# Sheet1.net
KiCad netlist of a schematic drawn in Altium Designer
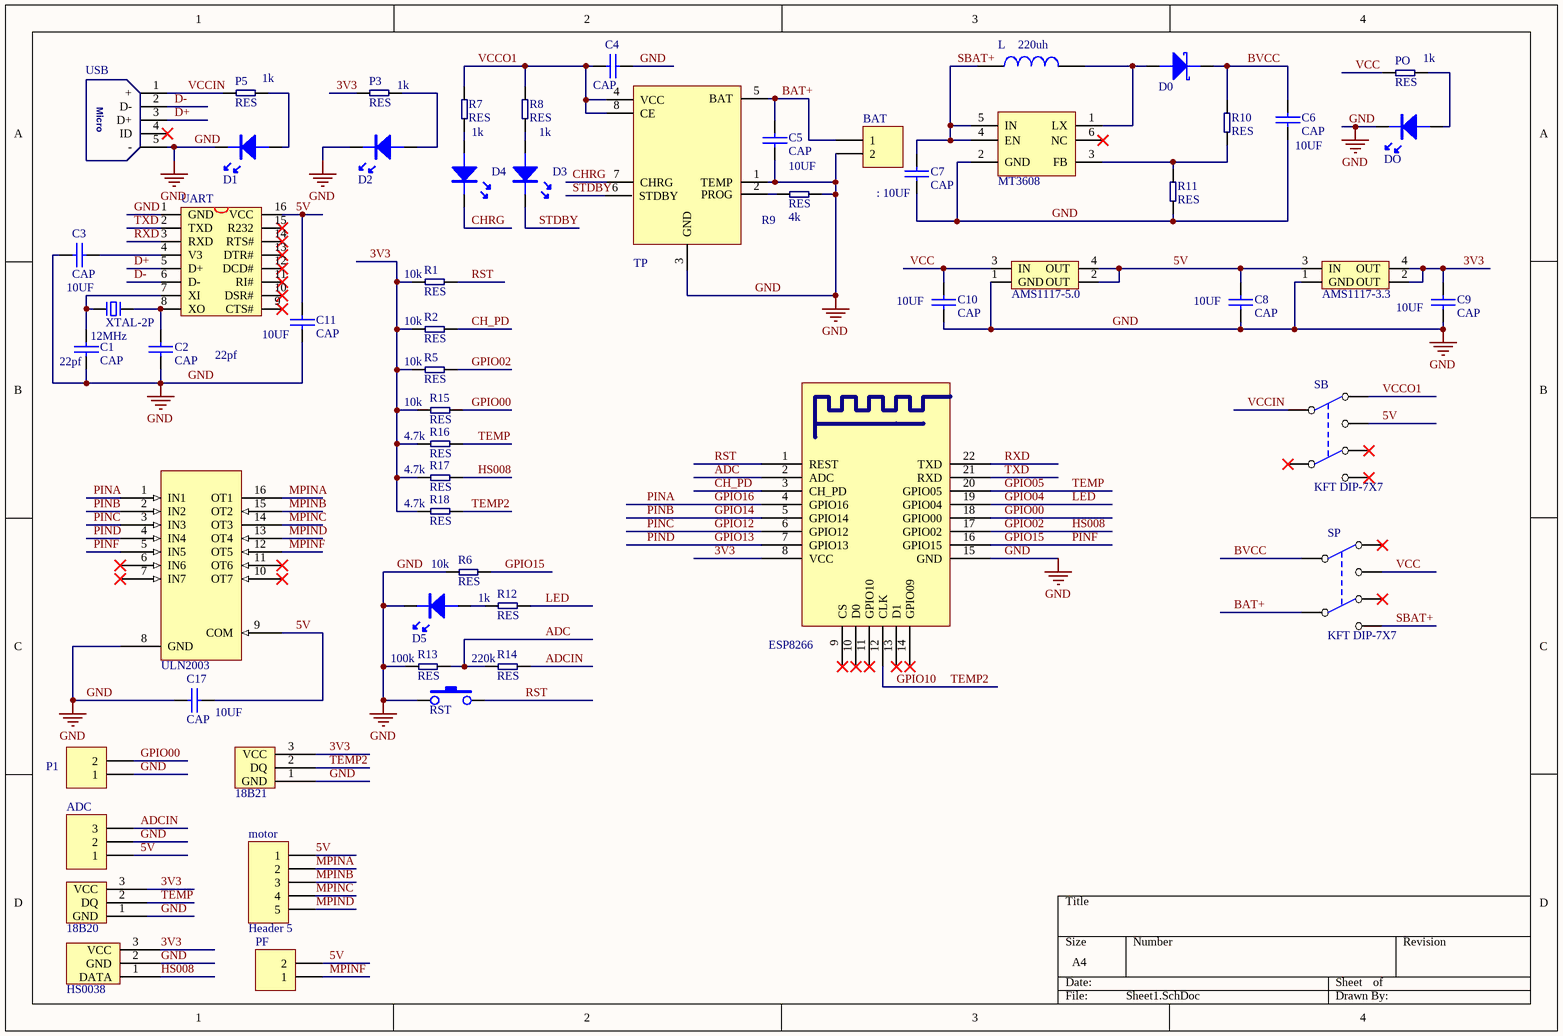
[diagram p0: Sheet1.SchDoc]

(export (version "E")
  (design (tool "Eeschema 10.0.6"))
  (components
    (comp (ref "18B20")
      (value "DS18B20")
      (footprint "DS18B20")
      (libsource (lib "MiniSTM32 V3.0封装库") (part "DS18B20"))
    )
    (comp (ref "18B21")
      (value "DS18B20")
      (footprint "DS18B20")
      (libsource (lib "MiniSTM32 V3.0封装库") (part "DS18B20"))
    )
    (comp (ref "ADC")
      (value "Header 3")
      (footprint "HDR1X3")
      (description "Header, 3-Pin")
      (fields (field (name "PUBLISHER") "Altium Limited"))
      (libsource (lib "Miscellaneous Connectors") (part "Header 3"))
    )
    (comp (ref "AMS117")
      (value "AMS1117-3.3")
      (footprint "AMS1117")
      (libsource (lib "MiniSTM32 V3.0封装库") (part "AMS1117"))
    )
    (comp (ref "AMS117-1")
      (value "AMS1117-5.0")
      (footprint "AMS1117")
      (libsource (lib "MiniSTM32 V3.0封装库") (part "AMS1117"))
    )
    (comp (ref "BAT")
      (value "Header 2")
      (footprint "HDR1X2")
      (description "Header, 2-Pin")
      (fields (field (name "PUBLISHER") "Altium Limited"))
      (libsource (lib "Miscellaneous Connectors") (part "Header 2"))
    )
    (comp (ref "C1")
      (value "CAP")
      (footprint "0805C")
      (description "无极性电容")
      (fields (field (name "ALTIUM_UNNAMED_1") "22pf"))
      (libsource (lib "电容") (part "CAP"))
    )
    (comp (ref "C2")
      (value "CAP")
      (footprint "0805C")
      (description "无极性电容")
      (fields (field (name "ALTIUM_UNNAMED_1") "22pf"))
      (libsource (lib "电容") (part "CAP"))
    )
    (comp (ref "C3")
      (value "CAP")
      (footprint "0805C")
      (description "无极性电容")
      (fields (field (name "ALTIUM_UNNAMED_1") "10UF"))
      (libsource (lib "电容") (part "CAP"))
    )
    (comp (ref "C4")
      (value "CAP")
      (footprint "0805C")
      (description "无极性电容")
      (libsource (lib "电容") (part "CAP"))
    )
    (comp (ref "C5")
      (value "CAP")
      (footprint "0805C")
      (description "无极性电容")
      (fields (field (name "ALTIUM_UNNAMED_1") "10UF"))
      (libsource (lib "电容") (part "CAP"))
    )
    (comp (ref "C6")
      (value "CAP")
      (footprint "0805C")
      (description "无极性电容")
      (fields (field (name "ALTIUM_UNNAMED_1") "10UF"))
      (libsource (lib "电容") (part "CAP"))
    )
    (comp (ref "C7")
      (value "CAP")
      (footprint "0805C")
      (description "无极性电容")
      (fields (field (name "ALTIUM_UNNAMED_1") "10UF"))
      (libsource (lib "电容") (part "CAP"))
    )
    (comp (ref "C8")
      (value "CAP")
      (footprint "0805C")
      (description "无极性电容")
      (fields (field (name "ALTIUM_UNNAMED_1") "10UF"))
      (libsource (lib "电容") (part "CAP"))
    )
    (comp (ref "C9")
      (value "CAP")
      (footprint "0805C")
      (description "无极性电容")
      (fields (field (name "ALTIUM_UNNAMED_1") "10UF"))
      (libsource (lib "电容") (part "CAP"))
    )
    (comp (ref "C10")
      (value "CAP")
      (footprint "0805C")
      (description "无极性电容")
      (fields (field (name "ALTIUM_UNNAMED_1") "10UF"))
      (libsource (lib "电容") (part "CAP"))
    )
    (comp (ref "C11")
      (value "CAP")
      (footprint "0805C")
      (description "无极性电容")
      (fields (field (name "ALTIUM_UNNAMED_1") "10UF"))
      (libsource (lib "电容") (part "CAP"))
    )
    (comp (ref "C17")
      (value "CAP")
      (footprint "0805C")
      (description "无极性电容")
      (fields (field (name "ALTIUM_UNNAMED_1") "10UF"))
      (libsource (lib "电容") (part "CAP"))
    )
    (comp (ref "D0")
      (value "DIODE SCHOTTKY")
      (footprint "SMA/DO-214AC")
      (description "肖特基二极管")
      (libsource (lib "二极管") (part "DIODE SCHOTTKY"))
    )
    (comp (ref "D1") (value "LED") (footprint "LED-0805R") (libsource (lib "LED") (part "LED")))
    (comp (ref "D2") (value "LED") (footprint "LED-0805R") (libsource (lib "LED") (part "LED")))
    (comp (ref "D3") (value "LED") (footprint "LED-0805R") (libsource (lib "LED") (part "LED")))
    (comp (ref "D4") (value "LED") (footprint "LED-0805R") (libsource (lib "LED") (part "LED")))
    (comp (ref "D5") (value "LED") (footprint "LED-0805R") (libsource (lib "LED") (part "LED")))
    (comp (ref "DO") (value "LED") (footprint "LED-0805R") (libsource (lib "LED") (part "LED")))
    (comp (ref "ESP8266") (value "ESP8266") (footprint "ESP_12") (libsource (lib "传感器") (part "ESP8266")))
    (comp (ref "HS0038")
      (value "HS0038")
      (footprint "HS0038")
      (libsource (lib "MiniSTM32 V3.0封装库") (part "HS0038"))
    )
    (comp (ref "L")
      (value "INDUCTOR")
      (footprint "CD54")
      (fields (field (name "ALTIUM_UNNAMED_1") "220uh"))
      (libsource (lib "电感") (part "INDUCTOR"))
    )
    (comp (ref "motor")
      (value "Header 5")
      (footprint "HDR1X5")
      (description "Header, 5-Pin")
      (fields (field (name "PUBLISHER") "Altium Limited"))
      (libsource (lib "Miscellaneous Connectors") (part "Header 5"))
    )
    (comp (ref "MT") (value "MT3608") (footprint "SOT23-6") (libsource (lib "Schlib1") (part "MT3608")))
    (comp (ref "P1")
      (value "Header 2")
      (footprint "HDR1X2")
      (description "Header, 2-Pin")
      (fields (field (name "PUBLISHER") "Altium Limited"))
      (libsource (lib "") (part "Header 2_1"))
    )
    (comp (ref "P3")
      (value "RES")
      (footprint "0805R")
      (fields (field (name "ALTIUM_UNNAMED_1") "1k"))
      (libsource (lib "Schlib1") (part "RES"))
    )
    (comp (ref "P5")
      (value "RES")
      (footprint "0805R")
      (fields (field (name "ALTIUM_UNNAMED_1") "1k"))
      (libsource (lib "Schlib1") (part "RES"))
    )
    (comp (ref "PF")
      (value "Header 2")
      (footprint "HDR1X2")
      (description "Header, 2-Pin")
      (fields (field (name "PUBLISHER") "Altium Limited"))
      (libsource (lib "") (part "Header 2_1"))
    )
    (comp (ref "PO")
      (value "RES")
      (footprint "0805R")
      (fields (field (name "ALTIUM_UNNAMED_1") "1k"))
      (libsource (lib "Schlib1") (part "RES"))
    )
    (comp (ref "R1")
      (value "RES")
      (footprint "0805R")
      (fields (field (name "ALTIUM_UNNAMED_1") "10k"))
      (libsource (lib "Schlib1") (part "RES"))
    )
    (comp (ref "R2")
      (value "RES")
      (footprint "0805R")
      (fields (field (name "ALTIUM_UNNAMED_1") "10k"))
      (libsource (lib "Schlib1") (part "RES"))
    )
    (comp (ref "R5")
      (value "RES")
      (footprint "0805R")
      (fields (field (name "ALTIUM_UNNAMED_1") "10k"))
      (libsource (lib "Schlib1") (part "RES"))
    )
    (comp (ref "R6")
      (value "RES")
      (footprint "0805R")
      (fields (field (name "ALTIUM_UNNAMED_1") "10k"))
      (libsource (lib "Schlib1") (part "RES"))
    )
    (comp (ref "R7")
      (value "RES")
      (footprint "0805R")
      (fields (field (name "ALTIUM_UNNAMED_1") "1k"))
      (libsource (lib "Schlib1") (part "RES"))
    )
    (comp (ref "R8")
      (value "RES")
      (footprint "0805R")
      (fields (field (name "ALTIUM_UNNAMED_1") "1k"))
      (libsource (lib "Schlib1") (part "RES"))
    )
    (comp (ref "R9")
      (value "RES")
      (footprint "0805R")
      (fields (field (name "ALTIUM_UNNAMED_1") "4k"))
      (libsource (lib "Schlib1") (part "RES"))
    )
    (comp (ref "R10") (value "RES") (footprint "0805R") (libsource (lib "Schlib1") (part "RES")))
    (comp (ref "R11") (value "RES") (footprint "0805R") (libsource (lib "Schlib1") (part "RES")))
    (comp (ref "R12")
      (value "RES")
      (footprint "0805R")
      (fields (field (name "ALTIUM_UNNAMED_1") "1k"))
      (libsource (lib "Schlib1") (part "RES"))
    )
    (comp (ref "R13")
      (value "RES")
      (footprint "0805R")
      (fields (field (name "ALTIUM_UNNAMED_1") "100k"))
      (libsource (lib "Schlib1") (part "RES"))
    )
    (comp (ref "R14")
      (value "RES")
      (footprint "0805R")
      (fields (field (name "ALTIUM_UNNAMED_1") "220k"))
      (libsource (lib "Schlib1") (part "RES"))
    )
    (comp (ref "R15")
      (value "RES")
      (footprint "0805R")
      (fields (field (name "ALTIUM_UNNAMED_1") "10k"))
      (libsource (lib "Schlib1") (part "RES"))
    )
    (comp (ref "R16")
      (value "RES")
      (footprint "0805R")
      (fields (field (name "ALTIUM_UNNAMED_1") "4.7k"))
      (libsource (lib "Schlib1") (part "RES"))
    )
    (comp (ref "R17")
      (value "RES")
      (footprint "0805R")
      (fields (field (name "ALTIUM_UNNAMED_1") "4.7k"))
      (libsource (lib "Schlib1") (part "RES"))
    )
    (comp (ref "R18")
      (value "RES")
      (footprint "0805R")
      (fields (field (name "ALTIUM_UNNAMED_1") "4.7k"))
      (libsource (lib "Schlib1") (part "RES"))
    )
    (comp (ref "RST") (value "KEY") (footprint "DIP-3X6X4.3") (libsource (lib "轻触开关") (part "KEY")))
    (comp (ref "SB")
      (value "KFT DIP-7X7")
      (footprint "KFT DIP-7X7")
      (libsource (lib "电源开关") (part "KFT DIP-7X7"))
    )
    (comp (ref "SP")
      (value "KFT DIP-7X7")
      (footprint "KFT DIP-7X7")
      (libsource (lib "电源开关") (part "KFT DIP-7X7"))
    )
    (comp (ref "TP") (value "TP4056") (footprint "SOP-8") (libsource (lib "Schlib1") (part "TP4056")))
    (comp (ref "UART")
      (value "CH340G")
      (footprint "SOP16M")
      (description "USB2UART")
      (libsource (lib "MiniSTM32 V3.0封装库") (part "CH340G"))
    )
    (comp (ref "ULN2003") (value "ULN2003") (footprint "SOP16") (libsource (lib "未分类IC") (part "ULN2003")))
    (comp (ref "USB")
      (value "Micro-USB")
      (footprint "USB-MICRO_A")
      (libsource (lib "USB") (part "Micro-USB"))
    )
    (comp (ref "X")
      (value "XTAL-2P")
      (footprint "OSC HC-49S")
      (description "2脚无源脚晶振")
      (fields (field (name "ALTIUM_UNNAMED_1") "12MHz"))
      (libsource (lib "晶振") (part "XTAL-2P"))
    )
  )
  (nets
    (net (code "1") (name "/3V3") (class "Default")
      (node (ref "18B20") (pin "3") (pinfunction "VCC_3") (pintype "passive"))
      (node (ref "18B21") (pin "3") (pinfunction "VCC_3") (pintype "passive"))
      (node (ref "AMS117") (pin "2") (pinfunction "OUT_2") (pintype "passive"))
      (node (ref "AMS117") (pin "4") (pinfunction "OUT_4") (pintype "passive"))
      (node (ref "C9") (pin "2") (pinfunction "2_2") (pintype "passive"))
      (node (ref "ESP8266") (pin "8") (pinfunction "VCC_8") (pintype "passive"))
      (node (ref "HS0038") (pin "3") (pinfunction "VCC_3") (pintype "passive"))
      (node (ref "P3") (pin "1") (pinfunction "0_1") (pintype "passive"))
      (node (ref "R1") (pin "2") (pinfunction "1_2") (pintype "passive"))
      (node (ref "R15") (pin "1") (pinfunction "0_1") (pintype "passive"))
      (node (ref "R16") (pin "2") (pinfunction "1_2") (pintype "passive"))
      (node (ref "R17") (pin "2") (pinfunction "1_2") (pintype "passive"))
      (node (ref "R18") (pin "2") (pinfunction "1_2") (pintype "passive"))
      (node (ref "R2") (pin "2") (pinfunction "1_2") (pintype "passive"))
      (node (ref "R5") (pin "1") (pinfunction "0_1") (pintype "passive"))
    )
    (net (code "2") (name "/5V") (class "Default")
      (node (ref "ADC") (pin "1") (pinfunction "1_1") (pintype "passive"))
      (node (ref "AMS117") (pin "3") (pinfunction "IN_3") (pintype "passive"))
      (node (ref "AMS117-1") (pin "2") (pinfunction "OUT_2") (pintype "passive"))
      (node (ref "AMS117-1") (pin "4") (pinfunction "OUT_4") (pintype "passive"))
      (node (ref "C11") (pin "2") (pinfunction "2_2") (pintype "passive"))
      (node (ref "C17") (pin "2") (pinfunction "2_2") (pintype "passive"))
      (node (ref "C8") (pin "2") (pinfunction "2_2") (pintype "passive"))
      (node (ref "PF") (pin "2") (pinfunction "2_2") (pintype "passive"))
      (node (ref "SB") (pin "1") (pinfunction "1_1") (pintype "passive"))
      (node (ref "UART") (pin "16") (pinfunction "VCC_16") (pintype "passive"))
      (node (ref "ULN2003") (pin "9") (pinfunction "COM_9") (pintype "input"))
      (node (ref "motor") (pin "1") (pinfunction "1_1") (pintype "passive"))
    )
    (net (code "3") (name "/ADC") (class "Default")
      (node (ref "ESP8266") (pin "2") (pinfunction "ADC_2") (pintype "passive"))
      (node (ref "R13") (pin "2") (pinfunction "1_2") (pintype "passive"))
      (node (ref "R14") (pin "1") (pinfunction "0_1") (pintype "passive"))
    )
    (net (code "4") (name "/ADCIN") (class "Default")
      (node (ref "ADC") (pin "3") (pinfunction "3_3") (pintype "passive"))
      (node (ref "R14") (pin "2") (pinfunction "1_2") (pintype "passive"))
    )
    (net (code "5") (name "/BAT+") (class "Default")
      (node (ref "BAT") (pin "1") (pinfunction "1_1") (pintype "passive"))
      (node (ref "C5") (pin "2") (pinfunction "2_2") (pintype "passive"))
      (node (ref "SP") (pin "5") (pinfunction "5_5") (pintype "passive"))
      (node (ref "TP") (pin "5") (pinfunction "BAT_5") (pintype "passive"))
    )
    (net (code "6") (name "/BVCC") (class "Default")
      (node (ref "C6") (pin "2") (pinfunction "2_2") (pintype "passive"))
      (node (ref "D0") (pin "K") (pinfunction "K_K") (pintype "passive"))
      (node (ref "R10") (pin "2") (pinfunction "1_2") (pintype "passive"))
      (node (ref "SP") (pin "2") (pinfunction "2_2") (pintype "passive"))
    )
    (net (code "7") (name "/CHRG") (class "Default")
      (node (ref "D4") (pin "K") (pinfunction "K_K") (pintype "passive"))
      (node (ref "TP") (pin "7") (pinfunction "CHRG_7") (pintype "passive"))
    )
    (net (code "8") (name "/CH_PD") (class "Default")
      (node (ref "ESP8266") (pin "3") (pinfunction "CH_PD_3") (pintype "passive"))
      (node (ref "R2") (pin "1") (pinfunction "0_1") (pintype "passive"))
    )
    (net (code "9") (name "/D+") (class "Default")
      (node (ref "UART") (pin "5") (pinfunction "D+_5") (pintype "passive"))
      (node (ref "USB") (pin "3") (pinfunction "D+_3") (pintype "passive"))
    )
    (net (code "10") (name "/D-") (class "Default")
      (node (ref "UART") (pin "6") (pinfunction "D-_6") (pintype "passive"))
      (node (ref "USB") (pin "2") (pinfunction "D-_2") (pintype "passive"))
    )
    (net (code "11") (name "/GPIO00") (class "Default")
      (node (ref "ESP8266") (pin "18") (pinfunction "GPIO00_18") (pintype "passive"))
      (node (ref "P1") (pin "2") (pinfunction "2_2") (pintype "passive"))
      (node (ref "R15") (pin "2") (pinfunction "1_2") (pintype "passive"))
    )
    (net (code "12") (name "/GPIO02") (class "Default")
      (node (ref "ESP8266") (pin "17") (pinfunction "GPIO02_17") (pintype "passive"))
      (node (ref "HS0038") (pin "1") (pinfunction "DATA_1") (pintype "passive"))
      (node (ref "R17") (pin "1") (pinfunction "0_1") (pintype "passive"))
      (node (ref "R5") (pin "2") (pinfunction "1_2") (pintype "passive"))
    )
    (net (code "13") (name "/GPIO04") (class "Default")
      (node (ref "ESP8266") (pin "19") (pinfunction "GPIO04_19") (pintype "passive"))
      (node (ref "R12") (pin "2") (pinfunction "1_2") (pintype "passive"))
    )
    (net (code "14") (name "/GPIO05") (class "Default")
      (node (ref "18B20") (pin "2") (pinfunction "DQ_2") (pintype "passive"))
      (node (ref "ESP8266") (pin "20") (pinfunction "GPIO05_20") (pintype "passive"))
      (node (ref "R16") (pin "1") (pinfunction "0_1") (pintype "passive"))
    )
    (net (code "15") (name "/GPIO10") (class "Default")
      (node (ref "18B21") (pin "2") (pinfunction "DQ_2") (pintype "passive"))
      (node (ref "ESP8266") (pin "12") (pinfunction "CLK_12") (pintype "passive"))
      (node (ref "R18") (pin "1") (pinfunction "0_1") (pintype "passive"))
    )
    (net (code "16") (name "/GPIO12") (class "Default")
      (node (ref "ESP8266") (pin "6") (pinfunction "GPIO12_6") (pintype "passive"))
      (node (ref "ULN2003") (pin "3") (pinfunction "IN3_3") (pintype "input"))
    )
    (net (code "17") (name "/GPIO13") (class "Default")
      (node (ref "ESP8266") (pin "7") (pinfunction "GPIO13_7") (pintype "passive"))
      (node (ref "ULN2003") (pin "4") (pinfunction "IN4_4") (pintype "input"))
    )
    (net (code "18") (name "/GPIO14") (class "Default")
      (node (ref "ESP8266") (pin "5") (pinfunction "GPIO14_5") (pintype "passive"))
      (node (ref "ULN2003") (pin "2") (pinfunction "IN2_2") (pintype "input"))
    )
    (net (code "19") (name "/GPIO15") (class "Default")
      (node (ref "ESP8266") (pin "16") (pinfunction "GPIO15_16") (pintype "passive"))
      (node (ref "R6") (pin "2") (pinfunction "1_2") (pintype "passive"))
      (node (ref "ULN2003") (pin "5") (pinfunction "IN5_5") (pintype "input"))
    )
    (net (code "20") (name "/GPIO16") (class "Default")
      (node (ref "ESP8266") (pin "4") (pinfunction "GPIO16_4") (pintype "passive"))
      (node (ref "ULN2003") (pin "1") (pinfunction "IN1_1") (pintype "input"))
    )
    (net (code "21") (name "/MPINA") (class "Default")
      (node (ref "ULN2003") (pin "16") (pinfunction "OT1_16") (pintype "power_in"))
      (node (ref "motor") (pin "2") (pinfunction "2_2") (pintype "passive"))
    )
    (net (code "22") (name "/MPINB") (class "Default")
      (node (ref "ULN2003") (pin "15") (pinfunction "OT2_15") (pintype "input"))
      (node (ref "motor") (pin "3") (pinfunction "3_3") (pintype "passive"))
    )
    (net (code "23") (name "/MPINC") (class "Default")
      (node (ref "ULN2003") (pin "14") (pinfunction "OT3_14") (pintype "tri_state"))
      (node (ref "motor") (pin "4") (pinfunction "4_4") (pintype "passive"))
    )
    (net (code "24") (name "/MPIND") (class "Default")
      (node (ref "ULN2003") (pin "13") (pinfunction "OT4_13") (pintype "input"))
      (node (ref "motor") (pin "5") (pinfunction "5_5") (pintype "passive"))
    )
    (net (code "25") (name "/MPINF") (class "Default")
      (node (ref "PF") (pin "1") (pinfunction "1_1") (pintype "passive"))
      (node (ref "ULN2003") (pin "12") (pinfunction "OT5_12") (pintype "input"))
    )
    (net (code "26") (name "/RST") (class "Default")
      (node (ref "ESP8266") (pin "1") (pinfunction "REST_1") (pintype "passive"))
      (node (ref "R1") (pin "1") (pinfunction "0_1") (pintype "passive"))
      (node (ref "RST") (pin "3") (pinfunction "3_3") (pintype "passive"))
    )
    (net (code "27") (name "/RXD") (class "Default")
      (node (ref "ESP8266") (pin "22") (pinfunction "TXD_22") (pintype "passive"))
      (node (ref "UART") (pin "3") (pinfunction "RXD_3") (pintype "passive"))
    )
    (net (code "28") (name "/SBAT+") (class "Default")
      (node (ref "C7") (pin "2") (pinfunction "2_2") (pintype "passive"))
      (node (ref "L") (pin "1") (pinfunction "1_1") (pintype "passive"))
      (node (ref "MT") (pin "4") (pinfunction "EN_4") (pintype "passive"))
      (node (ref "MT") (pin "5") (pinfunction "IN_5") (pintype "passive"))
      (node (ref "SP") (pin "6") (pinfunction "6_6") (pintype "passive"))
    )
    (net (code "29") (name "/STDBY") (class "Default")
      (node (ref "D3") (pin "K") (pinfunction "K_K") (pintype "passive"))
      (node (ref "TP") (pin "6") (pinfunction "STDBY_6") (pintype "passive"))
    )
    (net (code "30") (name "/TXD") (class "Default")
      (node (ref "ESP8266") (pin "21") (pinfunction "RXD_21") (pintype "passive"))
      (node (ref "UART") (pin "2") (pinfunction "TXD_2") (pintype "passive"))
    )
    (net (code "31") (name "/VCC") (class "Default")
      (node (ref "AMS117-1") (pin "3") (pinfunction "IN_3") (pintype "passive"))
      (node (ref "C10") (pin "2") (pinfunction "2_2") (pintype "passive"))
      (node (ref "PO") (pin "1") (pinfunction "0_1") (pintype "passive"))
      (node (ref "SP") (pin "1") (pinfunction "1_1") (pintype "passive"))
    )
    (net (code "32") (name "/VCCIN") (class "Default")
      (node (ref "P5") (pin "1") (pinfunction "0_1") (pintype "passive"))
      (node (ref "SB") (pin "2") (pinfunction "2_2") (pintype "passive"))
      (node (ref "USB") (pin "1") (pinfunction "+_1") (pintype "passive"))
    )
    (net (code "33") (name "/VCCO1") (class "Default")
      (node (ref "C4") (pin "1") (pinfunction "1_1") (pintype "passive"))
      (node (ref "R7") (pin "2") (pinfunction "1_2") (pintype "passive"))
      (node (ref "R8") (pin "2") (pinfunction "1_2") (pintype "passive"))
      (node (ref "SB") (pin "3") (pinfunction "3_3") (pintype "passive"))
      (node (ref "TP") (pin "4") (pinfunction "VCC_4") (pintype "passive"))
      (node (ref "TP") (pin "8") (pinfunction "CE_8") (pintype "passive"))
    )
    (net (code "34") (name "GND") (class "Default")
      (node (ref "18B20") (pin "1") (pinfunction "GND_1") (pintype "passive"))
      (node (ref "18B21") (pin "1") (pinfunction "GND_1") (pintype "passive"))
      (node (ref "ADC") (pin "2") (pinfunction "2_2") (pintype "passive"))
      (node (ref "AMS117") (pin "1") (pinfunction "GND_1") (pintype "passive"))
      (node (ref "AMS117-1") (pin "1") (pinfunction "GND_1") (pintype "passive"))
      (node (ref "BAT") (pin "2") (pinfunction "2_2") (pintype "passive"))
      (node (ref "C1") (pin "1") (pinfunction "1_1") (pintype "passive"))
      (node (ref "C10") (pin "1") (pinfunction "1_1") (pintype "passive"))
      (node (ref "C11") (pin "1") (pinfunction "1_1") (pintype "passive"))
      (node (ref "C17") (pin "1") (pinfunction "1_1") (pintype "passive"))
      (node (ref "C2") (pin "1") (pinfunction "1_1") (pintype "passive"))
      (node (ref "C3") (pin "2") (pinfunction "2_2") (pintype "passive"))
      (node (ref "C4") (pin "2") (pinfunction "2_2") (pintype "passive"))
      (node (ref "C5") (pin "1") (pinfunction "1_1") (pintype "passive"))
      (node (ref "C6") (pin "1") (pinfunction "1_1") (pintype "passive"))
      (node (ref "C7") (pin "1") (pinfunction "1_1") (pintype "passive"))
      (node (ref "C8") (pin "1") (pinfunction "1_1") (pintype "passive"))
      (node (ref "C9") (pin "1") (pinfunction "1_1") (pintype "passive"))
      (node (ref "D1") (pin "K") (pinfunction "K_K") (pintype "passive"))
      (node (ref "D2") (pin "K") (pinfunction "K_K") (pintype "passive"))
      (node (ref "D5") (pin "K") (pinfunction "K_K") (pintype "passive"))
      (node (ref "DO") (pin "K") (pinfunction "K_K") (pintype "passive"))
      (node (ref "ESP8266") (pin "15") (pinfunction "GND_15") (pintype "passive"))
      (node (ref "HS0038") (pin "2") (pinfunction "GND_2") (pintype "passive"))
      (node (ref "MT") (pin "2") (pinfunction "GND_2") (pintype "passive"))
      (node (ref "P1") (pin "1") (pinfunction "1_1") (pintype "passive"))
      (node (ref "R11") (pin "2") (pinfunction "1_2") (pintype "passive"))
      (node (ref "R13") (pin "1") (pinfunction "0_1") (pintype "passive"))
      (node (ref "R6") (pin "1") (pinfunction "0_1") (pintype "passive"))
      (node (ref "R9") (pin "1") (pinfunction "0_1") (pintype "passive"))
      (node (ref "RST") (pin "1") (pinfunction "1_1") (pintype "passive"))
      (node (ref "TP") (pin "1") (pinfunction "TEMP_1") (pintype "passive"))
      (node (ref "TP") (pin "3") (pinfunction "GND_3") (pintype "passive"))
      (node (ref "UART") (pin "1") (pinfunction "GND_1") (pintype "passive"))
      (node (ref "ULN2003") (pin "8") (pinfunction "GND_8") (pintype "power_in"))
      (node (ref "USB") (pin "5") (pinfunction "-_5") (pintype "passive"))
    )
    (net (code "35") (name "Net-(MT-FB)") (class "Default")
      (node (ref "MT") (pin "3") (pinfunction "FB_3") (pintype "passive"))
      (node (ref "R10") (pin "1") (pinfunction "0_1") (pintype "passive"))
      (node (ref "R11") (pin "1") (pinfunction "0_1") (pintype "passive"))
    )
    (net (code "36") (name "Net-(MT-LX)") (class "Default")
      (node (ref "D0") (pin "A") (pinfunction "A_A") (pintype "passive"))
      (node (ref "L") (pin "2") (pinfunction "2_2") (pintype "passive"))
      (node (ref "MT") (pin "1") (pinfunction "LX_1") (pintype "passive"))
    )
    (net (code "37") (name "Net-(P3-1)") (class "Default")
      (node (ref "D2") (pin "A") (pinfunction "A_A") (pintype "passive"))
      (node (ref "P3") (pin "2") (pinfunction "1_2") (pintype "passive"))
    )
    (net (code "38") (name "Net-(P5-1)") (class "Default")
      (node (ref "D1") (pin "A") (pinfunction "A_A") (pintype "passive"))
      (node (ref "P5") (pin "2") (pinfunction "1_2") (pintype "passive"))
    )
    (net (code "39") (name "Net-(PO-1)") (class "Default")
      (node (ref "DO") (pin "A") (pinfunction "A_A") (pintype "passive"))
      (node (ref "PO") (pin "2") (pinfunction "1_2") (pintype "passive"))
    )
    (net (code "40") (name "Net-(R7-0)") (class "Default")
      (node (ref "D4") (pin "A") (pinfunction "A_A") (pintype "passive"))
      (node (ref "R7") (pin "1") (pinfunction "0_1") (pintype "passive"))
    )
    (net (code "41") (name "Net-(R8-0)") (class "Default")
      (node (ref "D3") (pin "A") (pinfunction "A_A") (pintype "passive"))
      (node (ref "R8") (pin "1") (pinfunction "0_1") (pintype "passive"))
    )
    (net (code "42") (name "Net-(R9-1)") (class "Default")
      (node (ref "R9") (pin "2") (pinfunction "1_2") (pintype "passive"))
      (node (ref "TP") (pin "2") (pinfunction "PROG_2") (pintype "passive"))
    )
    (net (code "43") (name "Net-(R12-0)") (class "Default")
      (node (ref "D5") (pin "A") (pinfunction "A_A") (pintype "passive"))
      (node (ref "R12") (pin "1") (pinfunction "0_1") (pintype "passive"))
    )
    (net (code "44") (name "Net-(UART-V3)") (class "Default")
      (node (ref "C3") (pin "1") (pinfunction "1_1") (pintype "passive"))
      (node (ref "UART") (pin "4") (pinfunction "V3_4") (pintype "passive"))
    )
    (net (code "45") (name "Net-(UART-XI)") (class "Default")
      (node (ref "C1") (pin "2") (pinfunction "2_2") (pintype "passive"))
      (node (ref "UART") (pin "7") (pinfunction "XI_7") (pintype "passive"))
      (node (ref "X") (pin "2") (pinfunction "2_2") (pintype "passive"))
    )
    (net (code "46") (name "Net-(UART-XO)") (class "Default")
      (node (ref "C2") (pin "2") (pinfunction "2_2") (pintype "passive"))
      (node (ref "UART") (pin "8") (pinfunction "XO_8") (pintype "passive"))
      (node (ref "X") (pin "1") (pinfunction "1_1") (pintype "passive"))
    )
    (net (code "47") (name "unconnected-(ESP8266-CS-Pad9)") (class "Default")
      (node (ref "ESP8266") (pin "9") (pinfunction "CS_9") (pintype "passive+no_connect"))
    )
    (net (code "48") (name "unconnected-(ESP8266-D0-Pad10)") (class "Default")
      (node (ref "ESP8266") (pin "10") (pinfunction "D0_10") (pintype "passive+no_connect"))
    )
    (net (code "49") (name "unconnected-(ESP8266-D1-Pad13)") (class "Default")
      (node (ref "ESP8266") (pin "13") (pinfunction "D1_13") (pintype "passive+no_connect"))
    )
    (net (code "50") (name "unconnected-(ESP8266-GPIO09-Pad14)") (class "Default")
      (node (ref "ESP8266") (pin "14") (pinfunction "GPIO09_14") (pintype "passive+no_connect"))
    )
    (net (code "51") (name "unconnected-(ESP8266-GPIO10-Pad11)") (class "Default")
      (node (ref "ESP8266") (pin "11") (pinfunction "GPIO10_11") (pintype "passive+no_connect"))
    )
    (net (code "52") (name "unconnected-(MT-NC-Pad6)") (class "Default")
      (node (ref "MT") (pin "6") (pinfunction "NC_6") (pintype "passive+no_connect"))
    )
    (net (code "53") (name "unconnected-(SB-Pad4)") (class "Default")
      (node (ref "SB") (pin "4") (pinfunction "4_4") (pintype "passive+no_connect"))
    )
    (net (code "54") (name "unconnected-(SB-Pad5)") (class "Default")
      (node (ref "SB") (pin "5") (pinfunction "5_5") (pintype "passive+no_connect"))
    )
    (net (code "55") (name "unconnected-(SB-Pad6)") (class "Default")
      (node (ref "SB") (pin "6") (pinfunction "6_6") (pintype "passive+no_connect"))
    )
    (net (code "56") (name "unconnected-(SP-Pad3)") (class "Default")
      (node (ref "SP") (pin "3") (pinfunction "3_3") (pintype "passive+no_connect"))
    )
    (net (code "57") (name "unconnected-(SP-Pad4)") (class "Default")
      (node (ref "SP") (pin "4") (pinfunction "4_4") (pintype "passive+no_connect"))
    )
    (net (code "58") (name "unconnected-(UART-CTS#-Pad9)") (class "Default")
      (node (ref "UART") (pin "9") (pinfunction "CTS#_9") (pintype "passive+no_connect"))
    )
    (net (code "59") (name "unconnected-(UART-DCD#-Pad12)") (class "Default")
      (node (ref "UART") (pin "12") (pinfunction "DCD#_12") (pintype "passive+no_connect"))
    )
    (net (code "60") (name "unconnected-(UART-DSR#-Pad10)") (class "Default")
      (node (ref "UART") (pin "10") (pinfunction "DSR#_10") (pintype "passive+no_connect"))
    )
    (net (code "61") (name "unconnected-(UART-DTR#-Pad13)") (class "Default")
      (node (ref "UART") (pin "13") (pinfunction "DTR#_13") (pintype "passive+no_connect"))
    )
    (net (code "62") (name "unconnected-(UART-R232-Pad15)") (class "Default")
      (node (ref "UART") (pin "15") (pinfunction "R232_15") (pintype "passive+no_connect"))
    )
    (net (code "63") (name "unconnected-(UART-RI#-Pad11)") (class "Default")
      (node (ref "UART") (pin "11") (pinfunction "RI#_11") (pintype "passive+no_connect"))
    )
    (net (code "64") (name "unconnected-(UART-RTS#-Pad14)") (class "Default")
      (node (ref "UART") (pin "14") (pinfunction "RTS#_14") (pintype "passive+no_connect"))
    )
    (net (code "65") (name "unconnected-(ULN2003-IN6-Pad6)") (class "Default")
      (node (ref "ULN2003") (pin "6") (pinfunction "IN6_6") (pintype "input+no_connect"))
    )
    (net (code "66") (name "unconnected-(ULN2003-IN7-Pad7)") (class "Default")
      (node (ref "ULN2003") (pin "7") (pinfunction "IN7_7") (pintype "input+no_connect"))
    )
    (net (code "67") (name "unconnected-(ULN2003-OT6-Pad11)") (class "Default")
      (node (ref "ULN2003") (pin "11") (pinfunction "OT6_11") (pintype "input+no_connect"))
    )
    (net (code "68") (name "unconnected-(ULN2003-OT7-Pad10)") (class "Default")
      (node (ref "ULN2003") (pin "10") (pinfunction "OT7_10") (pintype "input+no_connect"))
    )
    (net (code "69") (name "unconnected-(USB-ID-Pad4)") (class "Default")
      (node (ref "USB") (pin "4") (pinfunction "ID_4") (pintype "passive+no_connect"))
    )
  )
)
